# easyeda1.net
KiCad netlist of a schematic drawn in EasyEDA
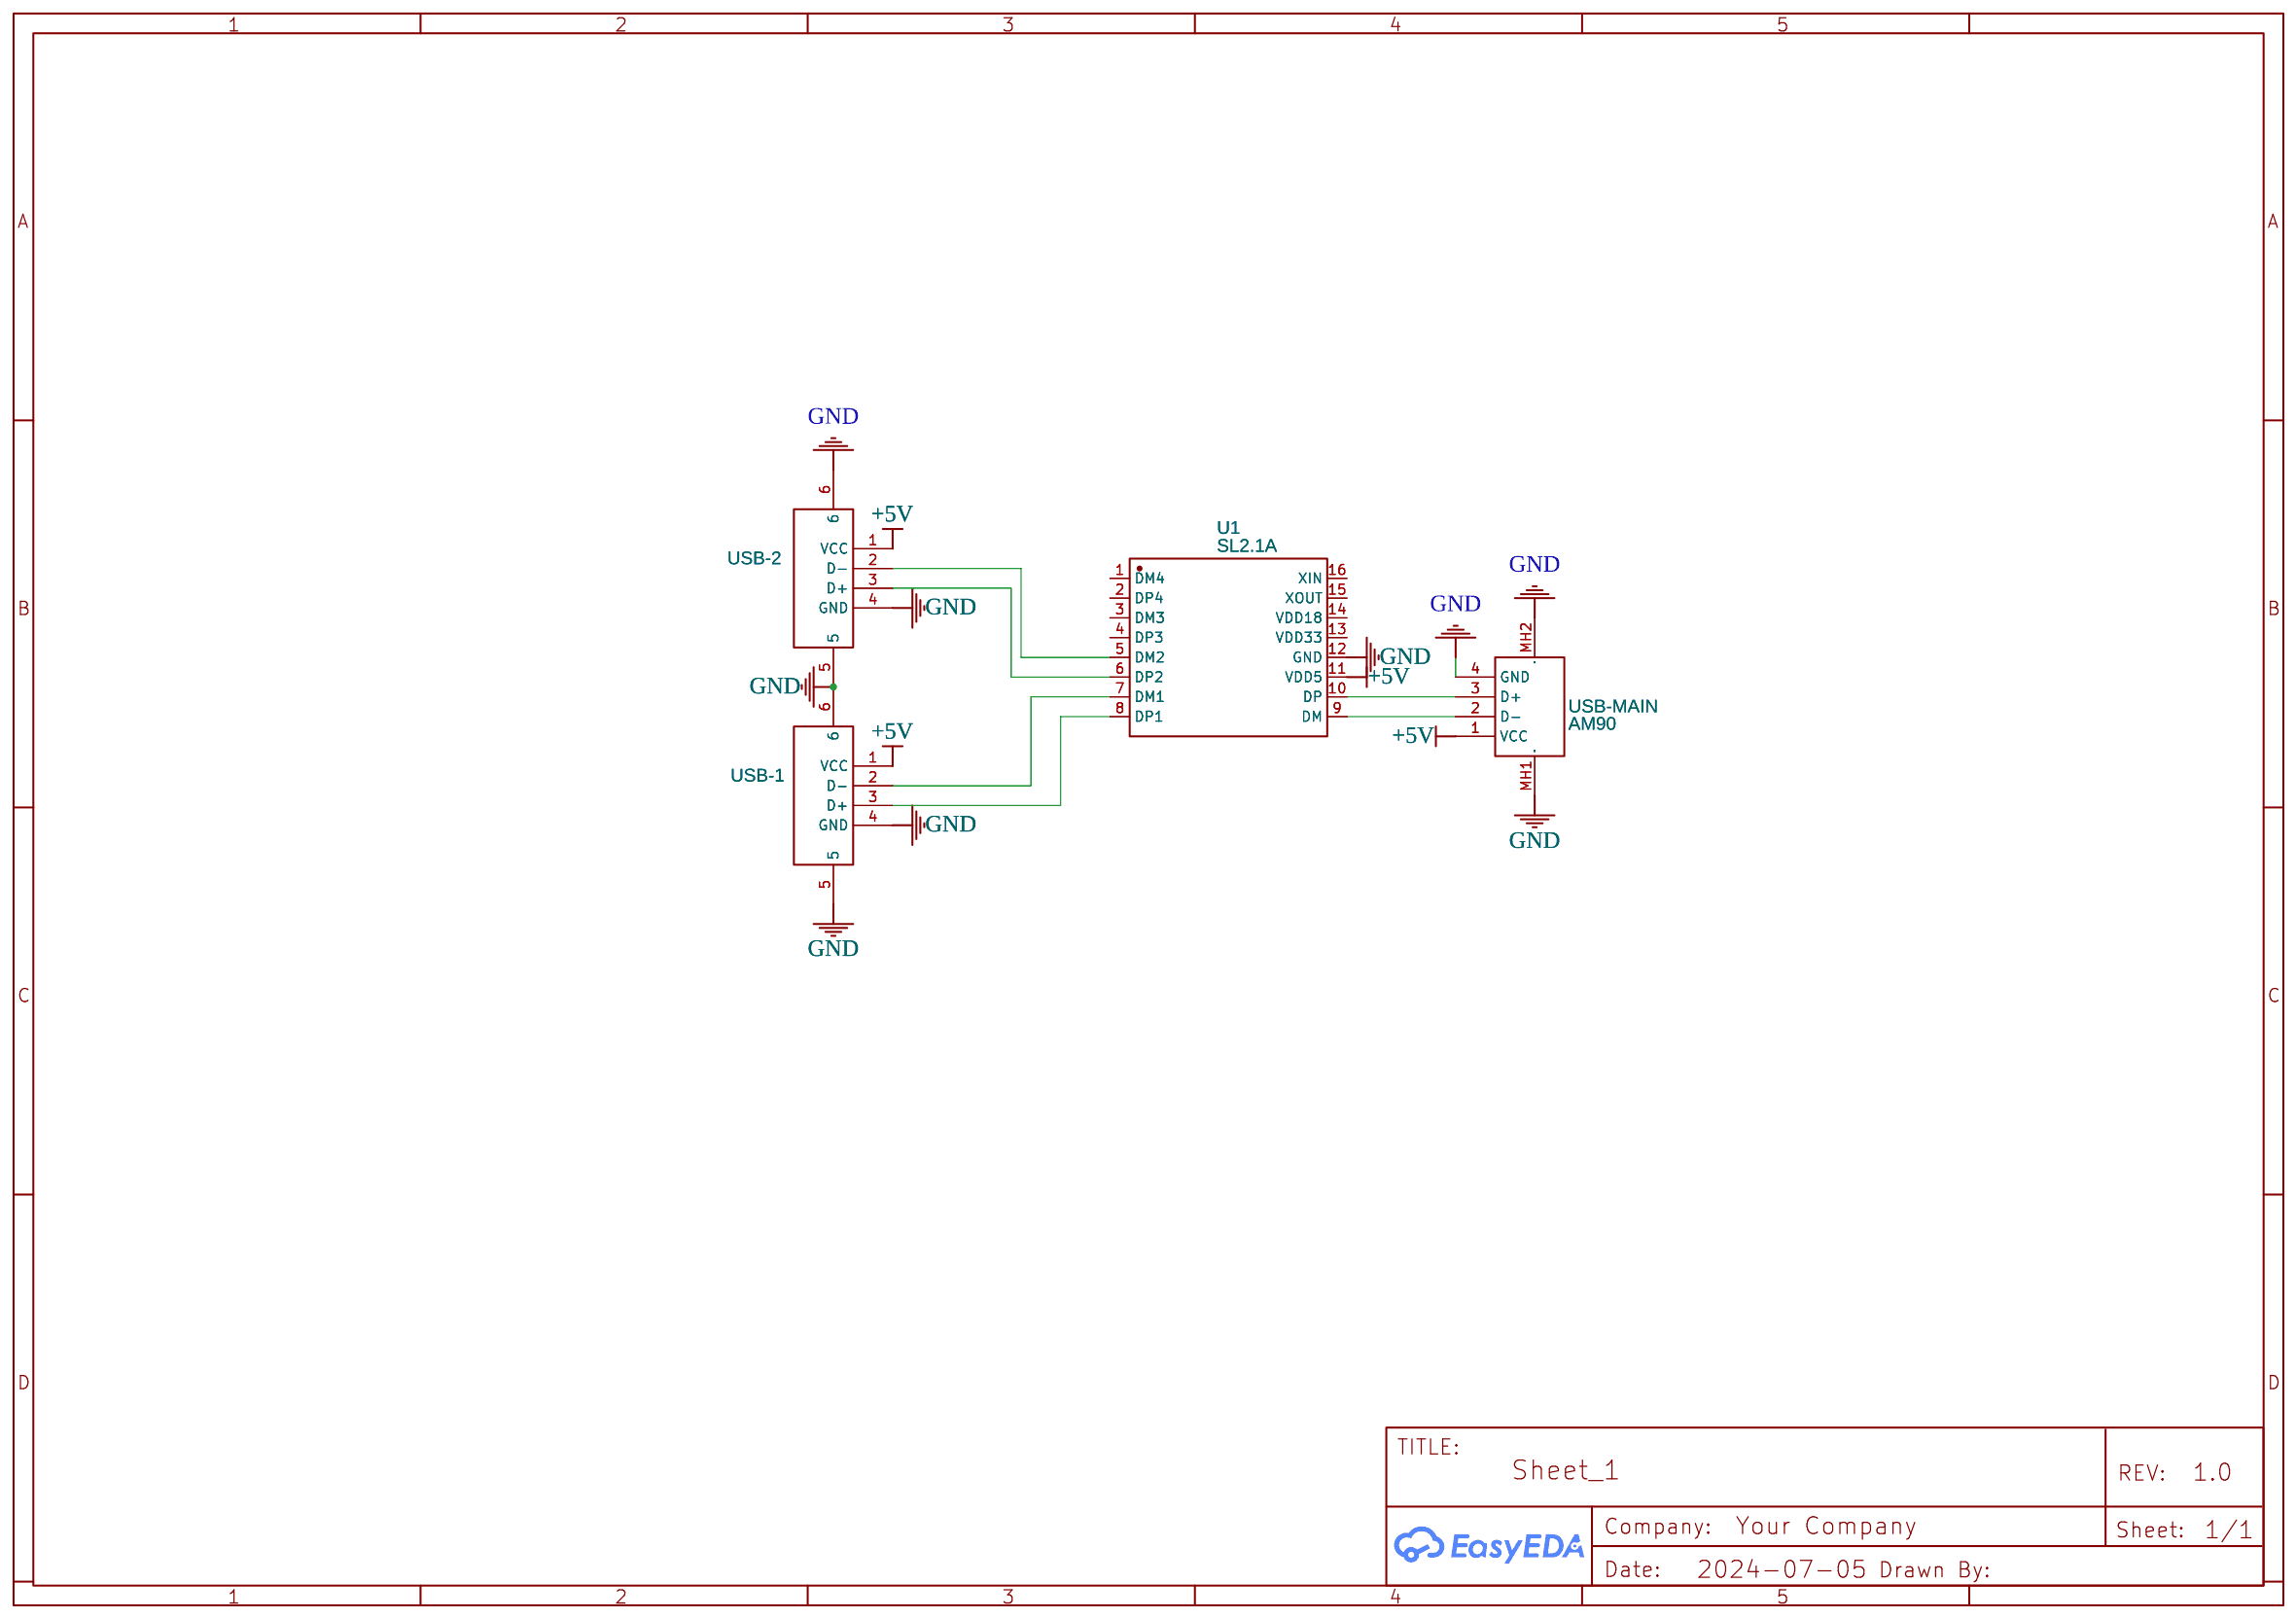
[diagram p0: schematic sheet]

(export (version "E")
  (design (tool "Eeschema 10.0.6"))
  (components
    (comp (ref "U1")
      (value "SL2.1A")
      (fields (field (name "Manufacturer") "CoreChips(和芯润德)"))
      (libsource (lib "") (part "SL2.1A"))
    )
    (comp (ref "USB-1")
      (value "USB-AF-90-14.4X13.6-H7.0-DIP")
      (fields (field (name "Manufacturer Part") "903-131A1011D10100") (field (name "Manufacturer") "精拓金"))
      (libsource (lib "") (part "USB-AF-90-14.4X13.6-H7.0-DIP"))
    )
    (comp (ref "USB-2")
      (value "USB-AF-90-14.4X13.6-H7.0-DIP")
      (fields (field (name "Manufacturer Part") "903-131A1011D10100") (field (name "Manufacturer") "精拓金"))
      (libsource (lib "") (part "USB-AF-90-14.4X13.6-H7.0-DIP"))
    )
    (comp (ref "USB-MAIN")
      (value "AM90")
      (fields (field (name "Manufacturer") "SHOU HAN(首韩)"))
      (libsource (lib "") (part "AM90"))
    )
  )
  (nets
    (net (code "1") (name "+5V") (class "Default")
      (node (ref "U1") (pin "11") (pinfunction "VDD5_11") (pintype "unspecified"))
      (node (ref "USB-1") (pin "1") (pinfunction "VCC_1") (pintype "unspecified"))
      (node (ref "USB-2") (pin "1") (pinfunction "VCC_1") (pintype "unspecified"))
      (node (ref "USB-MAIN") (pin "1") (pinfunction "VCC_1") (pintype "input"))
    )
    (net (code "2") (name "GND") (class "Default")
      (node (ref "U1") (pin "12") (pinfunction "GND_12") (pintype "unspecified"))
      (node (ref "USB-1") (pin "4") (pinfunction "GND_4") (pintype "unspecified"))
      (node (ref "USB-1") (pin "5") (pinfunction "5_5") (pintype "unspecified"))
      (node (ref "USB-1") (pin "6") (pinfunction "6_6") (pintype "unspecified"))
      (node (ref "USB-2") (pin "4") (pinfunction "GND_4") (pintype "unspecified"))
      (node (ref "USB-2") (pin "5") (pinfunction "5_5") (pintype "unspecified"))
      (node (ref "USB-2") (pin "6") (pinfunction "6_6") (pintype "unspecified"))
      (node (ref "USB-MAIN") (pin "4") (pinfunction "GND_4") (pintype "input"))
      (node (ref "USB-MAIN") (pin "MH1") (pinfunction "MH1_MH1") (pintype "unspecified"))
      (node (ref "USB-MAIN") (pin "MH2") (pinfunction "MH2_MH2") (pintype "unspecified"))
    )
    (net (code "3") (name "Net-(U1-DM)") (class "Default")
      (node (ref "U1") (pin "9") (pinfunction "DM_9") (pintype "unspecified"))
      (node (ref "USB-MAIN") (pin "2") (pinfunction "D-_2") (pintype "input"))
    )
    (net (code "4") (name "Net-(U1-DM1)") (class "Default")
      (node (ref "U1") (pin "7") (pinfunction "DM1_7") (pintype "unspecified"))
      (node (ref "USB-1") (pin "2") (pinfunction "D-_2") (pintype "unspecified"))
    )
    (net (code "5") (name "Net-(U1-DM2)") (class "Default")
      (node (ref "U1") (pin "5") (pinfunction "DM2_5") (pintype "unspecified"))
      (node (ref "USB-2") (pin "2") (pinfunction "D-_2") (pintype "unspecified"))
    )
    (net (code "6") (name "Net-(U1-DP)") (class "Default")
      (node (ref "U1") (pin "10") (pinfunction "DP_10") (pintype "unspecified"))
      (node (ref "USB-MAIN") (pin "3") (pinfunction "D+_3") (pintype "input"))
    )
    (net (code "7") (name "Net-(U1-DP1)") (class "Default")
      (node (ref "U1") (pin "8") (pinfunction "DP1_8") (pintype "unspecified"))
      (node (ref "USB-1") (pin "3") (pinfunction "D+_3") (pintype "unspecified"))
    )
    (net (code "8") (name "Net-(U1-DP2)") (class "Default")
      (node (ref "U1") (pin "6") (pinfunction "DP2_6") (pintype "unspecified"))
      (node (ref "USB-2") (pin "3") (pinfunction "D+_3") (pintype "unspecified"))
    )
    (net (code "9") (name "unconnected-(U1-DM3-Pad3)") (class "Default")
      (node (ref "U1") (pin "3") (pinfunction "DM3_3") (pintype "unspecified"))
    )
    (net (code "10") (name "unconnected-(U1-DM4-Pad1)") (class "Default")
      (node (ref "U1") (pin "1") (pinfunction "DM4_1") (pintype "unspecified"))
    )
    (net (code "11") (name "unconnected-(U1-DP3-Pad4)") (class "Default")
      (node (ref "U1") (pin "4") (pinfunction "DP3_4") (pintype "unspecified"))
    )
    (net (code "12") (name "unconnected-(U1-DP4-Pad2)") (class "Default")
      (node (ref "U1") (pin "2") (pinfunction "DP4_2") (pintype "unspecified"))
    )
    (net (code "13") (name "unconnected-(U1-VDD18-Pad14)") (class "Default")
      (node (ref "U1") (pin "14") (pinfunction "VDD18_14") (pintype "unspecified"))
    )
    (net (code "14") (name "unconnected-(U1-VDD33-Pad13)") (class "Default")
      (node (ref "U1") (pin "13") (pinfunction "VDD33_13") (pintype "unspecified"))
    )
    (net (code "15") (name "unconnected-(U1-XIN-Pad16)") (class "Default")
      (node (ref "U1") (pin "16") (pinfunction "XIN_16") (pintype "unspecified"))
    )
    (net (code "16") (name "unconnected-(U1-XOUT-Pad15)") (class "Default")
      (node (ref "U1") (pin "15") (pinfunction "XOUT_15") (pintype "unspecified"))
    )
  )
)
